# FWBC_v2.net
KiCad netlist of a schematic drawn in EAGLE
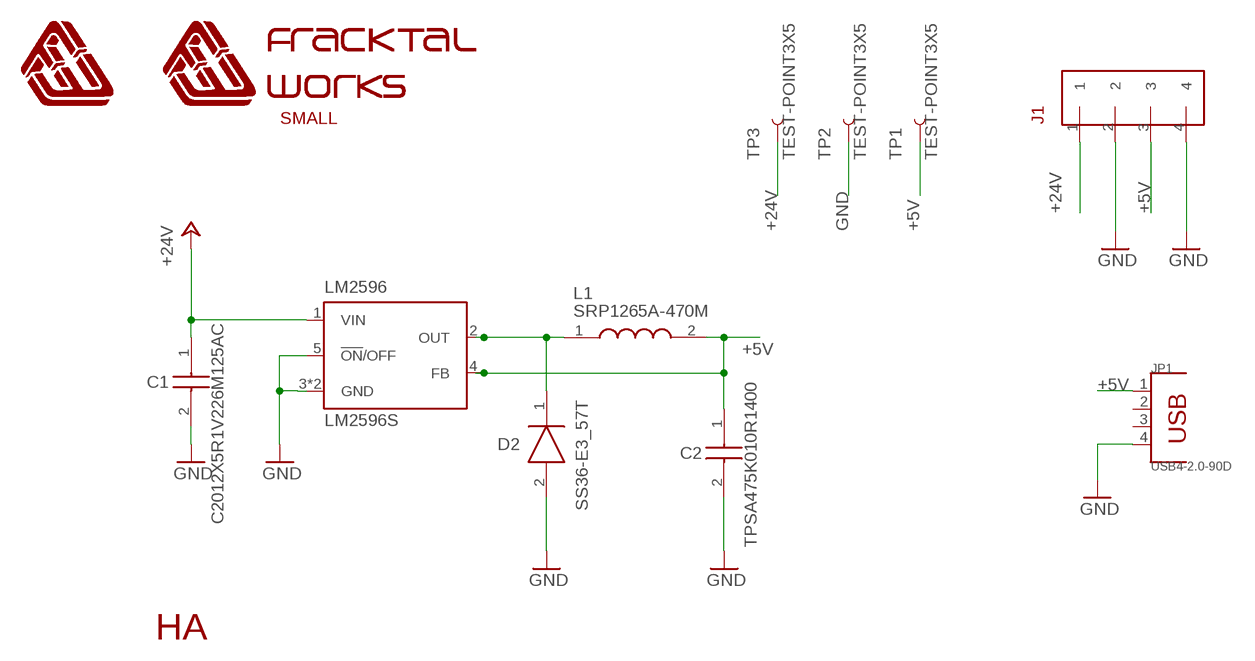
[diagram p0: schematic, sheet 1]

(export (version "E")
  (design (tool "Eeschema 10.0.6"))
  (components
    (comp (ref "C1")
      (value "C2012X5R1V226M125AC")
      (footprint "eagle-import:CAPC2012X145N")
      (fields
        (field (name "MOUSER_PART_NUMBER") "810-C2012X5R1V226MAC")
        (field (name "RS_PART_NUMBER") "9159334P")
      )
      (libsource (lib "eagle-import") (part "C2012X5R1V226M125AC"))
    )
    (comp (ref "C2")
      (value "TPSA475K010R1400")
      (footprint "eagle-import:CAPPM3216X180N")
      (fields
        (field (name "MOUSER_PART_NUMBER") "581-TPSA475K010R1400")
        (field (name "RS_PART_NUMBER") "1366129")
      )
      (libsource (lib "eagle-import") (part "TPSA475K010R1400"))
    )
    (comp (ref "D2")
      (value "SS36-E3_57T")
      (footprint "eagle-import:DIOM7959X262N")
      (fields
        (field (name "MANUFACTURER_PART_NUMBER") "SS36-E3/57T")
        (field (name "MOUSER_PART_NUMBER") "625-SS36-E3")
        (field (name "RS_PART_NUMBER") "7000975P")
      )
      (libsource (lib "eagle-import") (part "SS36-E3_57T"))
    )
    (comp (ref "J1")
      (value "TERMINALBLOCK/TOYO/4PIN/5MMPITCH")
      (footprint "eagle-import:TERMINALBLOCK_TOYO_4PIN_5MMPITCH")
      (libsource (lib "eagle-import") (part "TERMINALBLOCK/TOYO/4PIN/5MMPITCH"))
    )
    (comp (ref "JP1")
      (value "USB4-2.0-90D")
      (footprint "eagle-import:USB4+2P-2.0-90D")
      (libsource (lib "eagle-import") (part "DIP-USB-A-TYPE-FMAL(4+2P-2.0-90D)"))
    )
    (comp (ref "L1")
      (value "SRP1265A-470M")
      (footprint "eagle-import:SRP1265A")
      (fields
        (field (name "MOUSER_PART_NUMBER") "652-SRP1265A-470M")
        (field (name "RS_PART_NUMBER") "8193513P")
      )
      (libsource (lib "eagle-import") (part "SRP1265A-470M"))
    )
    (comp (ref "LM2596")
      (value "LM2596S")
      (footprint "eagle-import:LM2596_TO263-5")
      (fields (field (name "MF") "NATIONAL SEMICONDUCTOR") (field (name "MPN") "LM2596S-ADJ/NOPB"))
      (libsource (lib "eagle-import") (part "LM2596S"))
    )
    (comp (ref "M_HA_1")
      (value "HA_MARK")
      (footprint "eagle-import:HA_MARK")
      (libsource (lib "eagle-import") (part "HA_MARK"))
    )
    (comp (ref "TP1")
      (value "TEST-POINT3X5")
      (footprint "eagle-import:PAD.03X.05")
      (libsource (lib "eagle-import") (part "TEST-POINT3X5"))
    )
    (comp (ref "TP2")
      (value "TEST-POINT3X5")
      (footprint "eagle-import:PAD.03X.05")
      (libsource (lib "eagle-import") (part "TEST-POINT3X5"))
    )
    (comp (ref "TP3")
      (value "TEST-POINT3X5")
      (footprint "eagle-import:PAD.03X.05")
      (libsource (lib "eagle-import") (part "TEST-POINT3X5"))
    )
    (comp (ref "U$1")
      (value "FWLOGO")
      (footprint "eagle-import:FWLOGO")
      (libsource (lib "eagle-import") (part "FWLOGO"))
    )
    (comp (ref "U$2")
      (value "FWLOGO_TEXT_SMALL")
      (footprint "eagle-import:FWLOGO_TEXT_SMALL")
      (libsource (lib "eagle-import") (part "FWLOGO_TEXT_SMALL"))
    )
  )
  (nets
    (net (code "1") (name "+24V") (class "Default")
      (node (ref "C1") (pin "1") (pinfunction "1_1") (pintype "bidirectional"))
      (node (ref "J1") (pin "1") (pinfunction "1_1") (pintype "bidirectional"))
      (node (ref "LM2596") (pin "1") (pinfunction "VIN_1") (pintype "input"))
      (node (ref "TP3") (pin "P$1") (pinfunction "1_P$1") (pintype "bidirectional"))
    )
    (net (code "2") (name "/+5V") (class "Default")
      (node (ref "C2") (pin "1") (pinfunction "1_1") (pintype "bidirectional"))
      (node (ref "J1") (pin "3") (pinfunction "3_3") (pintype "bidirectional"))
      (node (ref "JP1") (pin "1") (pinfunction "1_1") (pintype "bidirectional"))
      (node (ref "L1") (pin "2") (pinfunction "2_2") (pintype "bidirectional"))
      (node (ref "LM2596") (pin "4") (pinfunction "FB_4") (pintype "input"))
      (node (ref "TP1") (pin "P$1") (pinfunction "1_P$1") (pintype "bidirectional"))
    )
    (net (code "3") (name "GND") (class "Default")
      (node (ref "C1") (pin "2") (pinfunction "2_2") (pintype "bidirectional"))
      (node (ref "C2") (pin "2") (pinfunction "2_2") (pintype "bidirectional"))
      (node (ref "D2") (pin "2") (pinfunction "A_2") (pintype "bidirectional"))
      (node (ref "J1") (pin "2") (pinfunction "2_2") (pintype "bidirectional"))
      (node (ref "J1") (pin "4") (pinfunction "4_4") (pintype "bidirectional"))
      (node (ref "JP1") (pin "4") (pinfunction "4_4") (pintype "bidirectional"))
      (node (ref "LM2596") (pin "3") (pinfunction "GND_3") (pintype "power_in"))
      (node (ref "LM2596") (pin "5") (pinfunction "~{ON}/OFF_5") (pintype "input"))
      (node (ref "LM2596") (pin "6") (pinfunction "GND_6") (pintype "power_in"))
      (node (ref "TP2") (pin "P$1") (pinfunction "1_P$1") (pintype "bidirectional"))
    )
    (net (code "4") (name "Net-(D2-K)") (class "Default")
      (node (ref "D2") (pin "1") (pinfunction "K_1") (pintype "bidirectional"))
      (node (ref "L1") (pin "1") (pinfunction "1_1") (pintype "bidirectional"))
      (node (ref "LM2596") (pin "2") (pinfunction "OUT_2") (pintype "output"))
    )
    (net (code "5") (name "unconnected-(JP1-Pad2)") (class "Default")
      (node (ref "JP1") (pin "2") (pinfunction "2_2") (pintype "bidirectional"))
    )
    (net (code "6") (name "unconnected-(JP1-Pad3)") (class "Default")
      (node (ref "JP1") (pin "3") (pinfunction "3_3") (pintype "bidirectional"))
    )
  )
)
